# SCH_555-thing_2026-06-18.net
KiCad netlist of a schematic drawn in EasyEDA
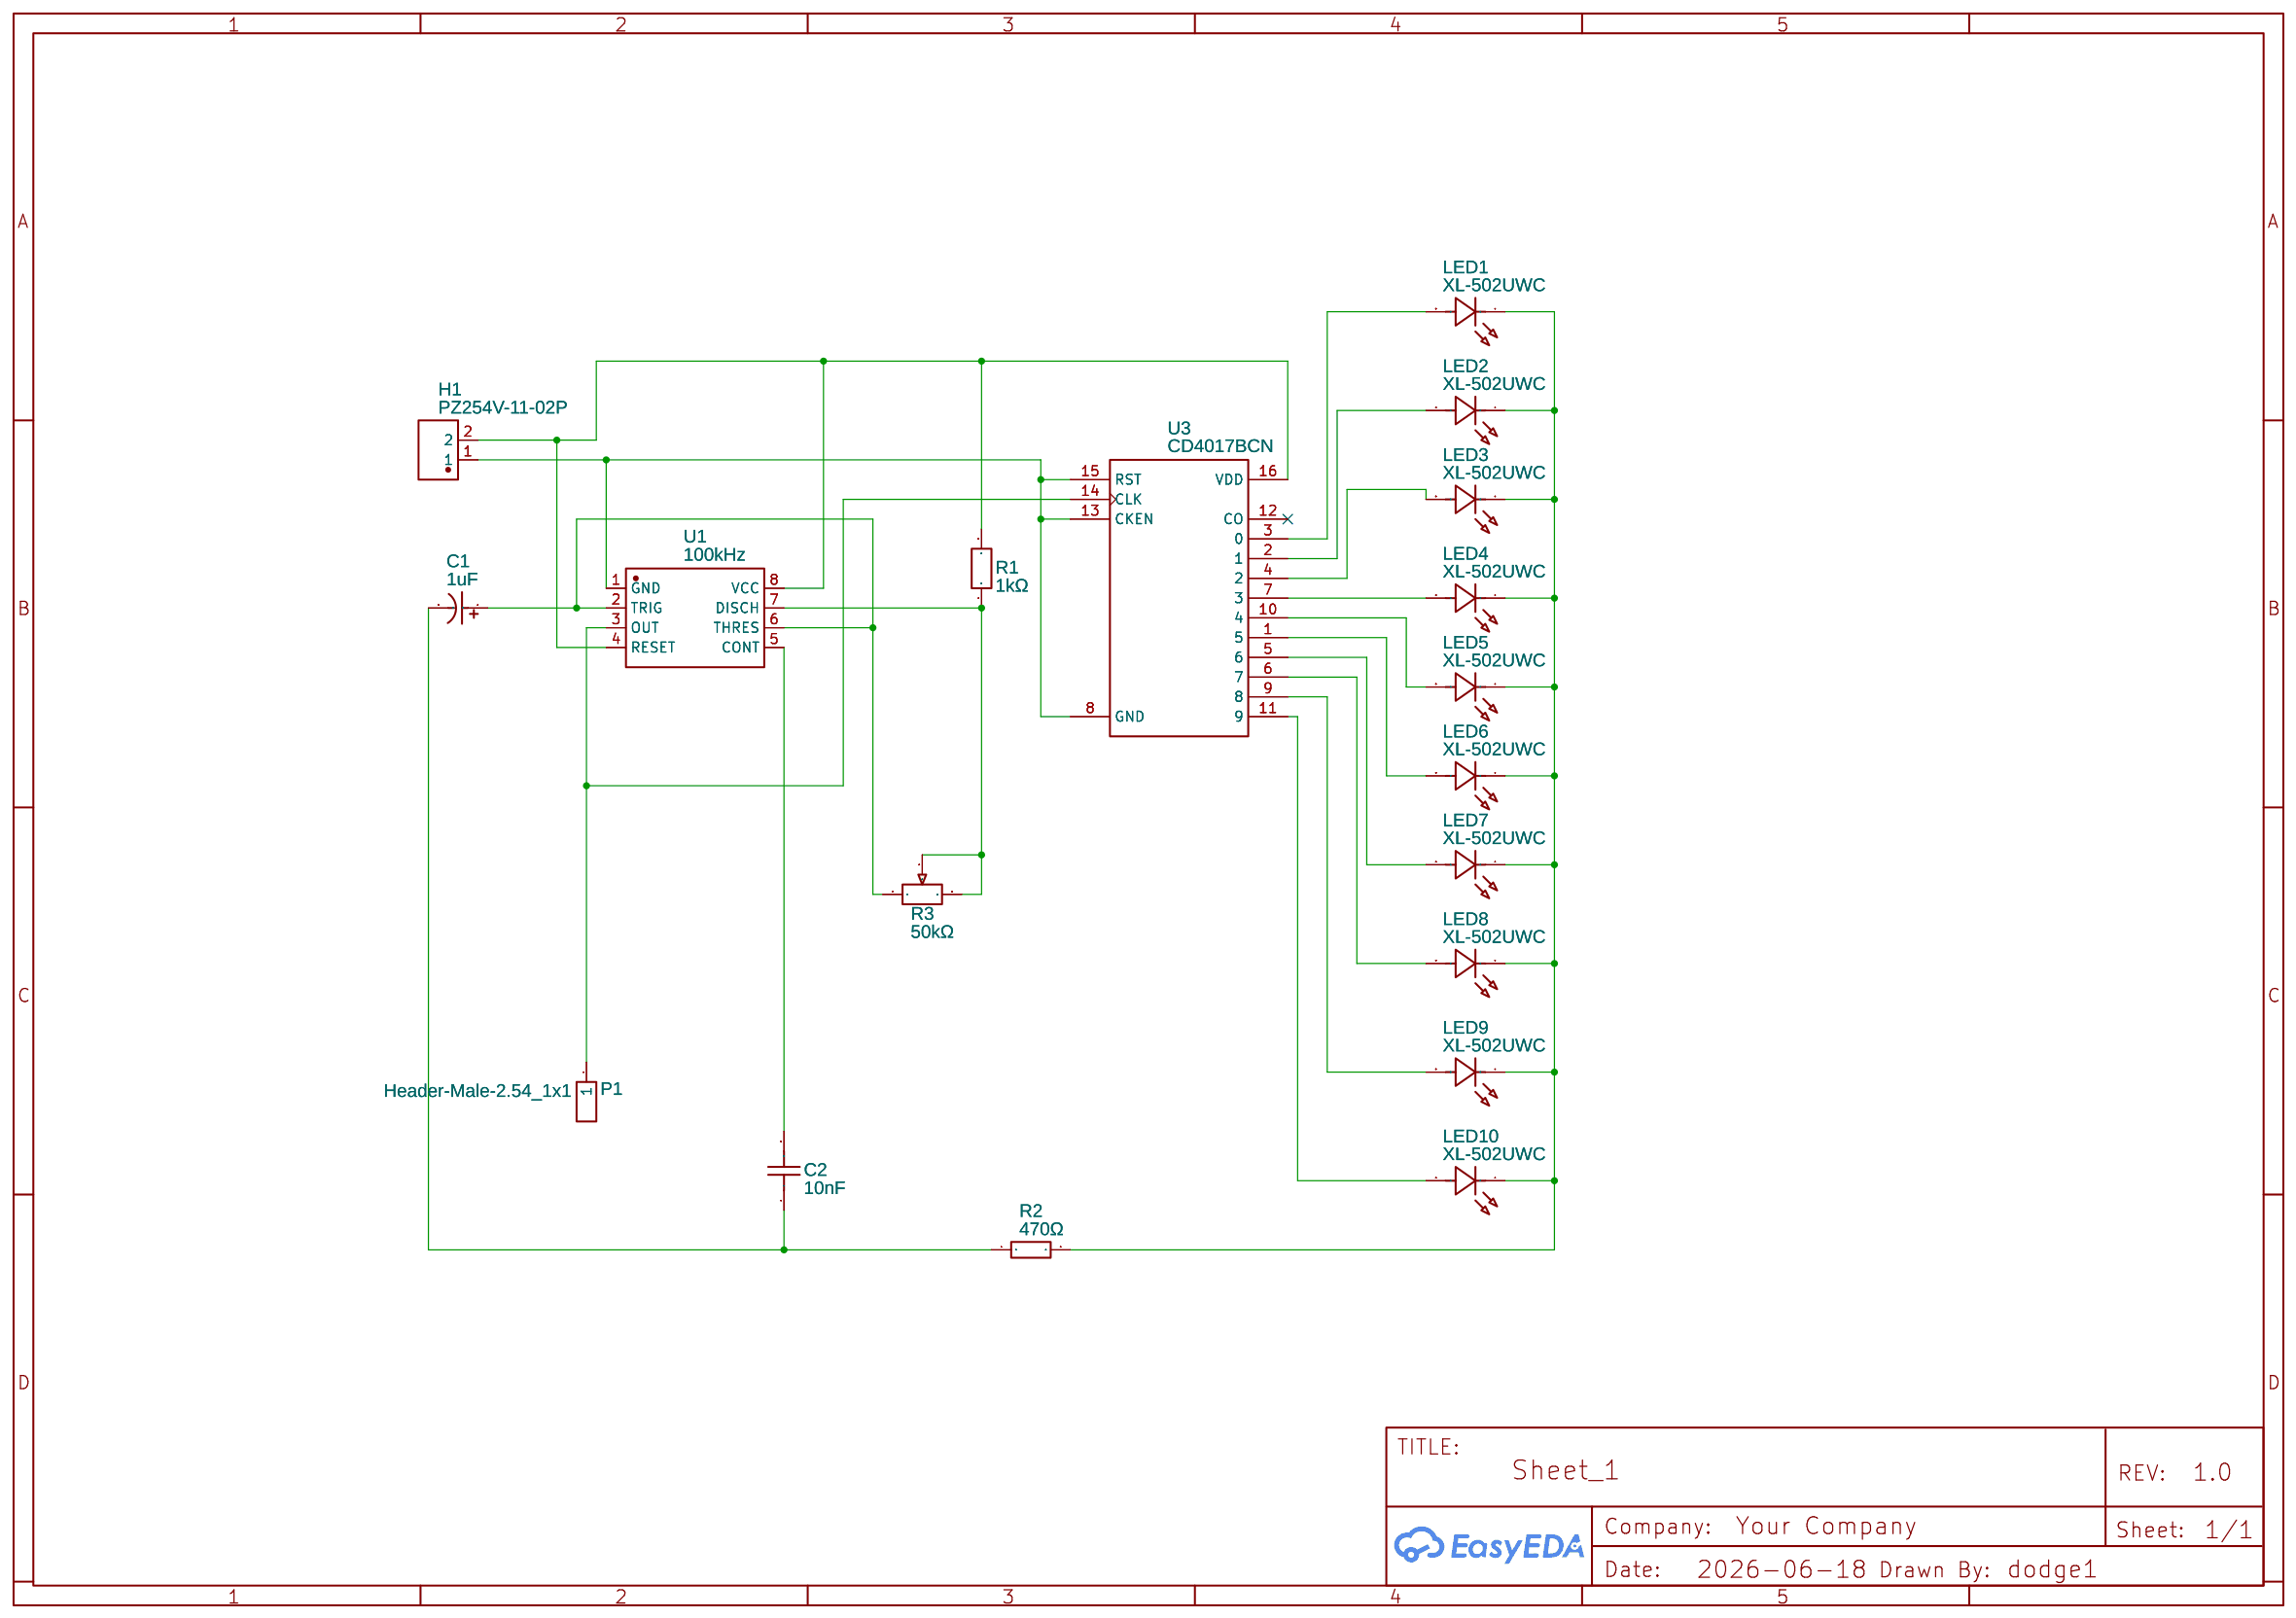
[diagram p0: schematic sheet]

(export (version "E")
  (design (tool "Eeschema 10.0.6"))
  (components
    (comp (ref "C1")
      (value "1uF")
      (fields (field (name "Manufacturer Part") "KF010M050C110A") (field (name "Manufacturer") "CapXon(丰宾)"))
      (libsource (lib "") (part "KF010M050C110A"))
    )
    (comp (ref "C2")
      (value "10nF")
      (fields (field (name "Manufacturer Part") "N09F1B103MN0B0S0N0") (field (name "Manufacturer") "STE(松田)"))
      (libsource (lib "") (part "N09F1B103MN0B0S0N0"))
    )
    (comp (ref "H1")
      (value "PZ254V-11-02P")
      (fields (field (name "Manufacturer") "XFCN(兴飞)"))
      (libsource (lib "") (part "PZ254V-11-02P"))
    )
    (comp (ref "LED1")
      (value "XL-502UWC")
      (fields (field (name "Manufacturer") "XINGLIGHT(成兴光)"))
      (libsource (lib "") (part "XL-502UWC"))
    )
    (comp (ref "LED2")
      (value "XL-502UWC")
      (fields (field (name "Manufacturer") "XINGLIGHT(成兴光)"))
      (libsource (lib "") (part "XL-502UWC"))
    )
    (comp (ref "LED3")
      (value "XL-502UWC")
      (fields (field (name "Manufacturer") "XINGLIGHT(成兴光)"))
      (libsource (lib "") (part "XL-502UWC"))
    )
    (comp (ref "LED4")
      (value "XL-502UWC")
      (fields (field (name "Manufacturer") "XINGLIGHT(成兴光)"))
      (libsource (lib "") (part "XL-502UWC"))
    )
    (comp (ref "LED5")
      (value "XL-502UWC")
      (fields (field (name "Manufacturer") "XINGLIGHT(成兴光)"))
      (libsource (lib "") (part "XL-502UWC"))
    )
    (comp (ref "LED6")
      (value "XL-502UWC")
      (fields (field (name "Manufacturer") "XINGLIGHT(成兴光)"))
      (libsource (lib "") (part "XL-502UWC"))
    )
    (comp (ref "LED7")
      (value "XL-502UWC")
      (fields (field (name "Manufacturer") "XINGLIGHT(成兴光)"))
      (libsource (lib "") (part "XL-502UWC"))
    )
    (comp (ref "LED8")
      (value "XL-502UWC")
      (fields (field (name "Manufacturer") "XINGLIGHT(成兴光)"))
      (libsource (lib "") (part "XL-502UWC"))
    )
    (comp (ref "LED9")
      (value "XL-502UWC")
      (fields (field (name "Manufacturer") "XINGLIGHT(成兴光)"))
      (libsource (lib "") (part "XL-502UWC"))
    )
    (comp (ref "LED10")
      (value "XL-502UWC")
      (fields (field (name "Manufacturer") "XINGLIGHT(成兴光)"))
      (libsource (lib "") (part "XL-502UWC"))
    )
    (comp (ref "P1")
      (value "Header-Male-2.54_1x1")
      (fields (field (name "Manufacturer Part") "2.54-1*1P针") (field (name "Manufacturer") "BOOMELE(博穆精密)"))
      (libsource (lib "") (part "Header-Male-2.54_1x1"))
    )
    (comp (ref "R1")
      (value "1kΩ")
      (fields (field (name "Manufacturer Part") "MF1/4W-1KΩ±1%T52") (field (name "Manufacturer") "华星机电"))
      (libsource (lib "") (part "MF1/4W-1KΩ±1%T52"))
    )
    (comp (ref "R2")
      (value "470Ω")
      (fields
        (field (name "Manufacturer Part") "MFR0W4F4700A50")
        (field (name "Manufacturer") "UNI-ROYAL(厚声)")
      )
      (libsource (lib "") (part "MFR0W4F4700A50"))
    )
    (comp (ref "R3")
      (value "50kΩ")
      (fields (field (name "Manufacturer Part") "3296X-1-503") (field (name "Manufacturer") "BOCHEN(博晨)"))
      (libsource (lib "") (part "3296X-1-503_C118912"))
    )
    (comp (ref "U1")
      (value "100kHz")
      (fields (field (name "Manufacturer Part") "NE555P") (field (name "Manufacturer") "TI(德州仪器)"))
      (libsource (lib "") (part "NE555P"))
    )
    (comp (ref "U3") (value "CD4017BCN") (libsource (lib "") (part "CD4017BCN")))
  )
  (nets
    (net (code "1") (name "Net-(C1-Pad2)") (class "Default")
      (node (ref "C1") (pin "2") (pinfunction "2_2") (pintype "input"))
      (node (ref "C2") (pin "1") (pinfunction "1_1") (pintype "unspecified"))
      (node (ref "R2") (pin "1") (pinfunction "1_1") (pintype "input"))
    )
    (net (code "2") (name "Net-(LED1-A)") (class "Default")
      (node (ref "LED1") (pin "2") (pinfunction "A_2") (pintype "unspecified"))
      (node (ref "U3") (pin "3") (pinfunction "0_3") (pintype "output"))
    )
    (net (code "3") (name "Net-(LED1-K)") (class "Default")
      (node (ref "LED1") (pin "1") (pinfunction "K_1") (pintype "unspecified"))
      (node (ref "LED10") (pin "1") (pinfunction "K_1") (pintype "unspecified"))
      (node (ref "LED2") (pin "1") (pinfunction "K_1") (pintype "unspecified"))
      (node (ref "LED3") (pin "1") (pinfunction "K_1") (pintype "unspecified"))
      (node (ref "LED4") (pin "1") (pinfunction "K_1") (pintype "unspecified"))
      (node (ref "LED5") (pin "1") (pinfunction "K_1") (pintype "unspecified"))
      (node (ref "LED6") (pin "1") (pinfunction "K_1") (pintype "unspecified"))
      (node (ref "LED7") (pin "1") (pinfunction "K_1") (pintype "unspecified"))
      (node (ref "LED8") (pin "1") (pinfunction "K_1") (pintype "unspecified"))
      (node (ref "LED9") (pin "1") (pinfunction "K_1") (pintype "unspecified"))
      (node (ref "R2") (pin "2") (pinfunction "2_2") (pintype "input"))
    )
    (net (code "4") (name "Net-(LED2-A)") (class "Default")
      (node (ref "LED2") (pin "2") (pinfunction "A_2") (pintype "unspecified"))
      (node (ref "U3") (pin "2") (pinfunction "1_2") (pintype "output"))
    )
    (net (code "5") (name "Net-(LED3-A)") (class "Default")
      (node (ref "LED3") (pin "2") (pinfunction "A_2") (pintype "unspecified"))
      (node (ref "U3") (pin "4") (pinfunction "2_4") (pintype "output"))
    )
    (net (code "6") (name "Net-(LED4-A)") (class "Default")
      (node (ref "LED4") (pin "2") (pinfunction "A_2") (pintype "unspecified"))
      (node (ref "U3") (pin "7") (pinfunction "3_7") (pintype "output"))
    )
    (net (code "7") (name "Net-(LED5-A)") (class "Default")
      (node (ref "LED5") (pin "2") (pinfunction "A_2") (pintype "unspecified"))
      (node (ref "U3") (pin "10") (pinfunction "4_10") (pintype "output"))
    )
    (net (code "8") (name "Net-(LED6-A)") (class "Default")
      (node (ref "LED6") (pin "2") (pinfunction "A_2") (pintype "unspecified"))
      (node (ref "U3") (pin "1") (pinfunction "5_1") (pintype "output"))
    )
    (net (code "9") (name "Net-(LED7-A)") (class "Default")
      (node (ref "LED7") (pin "2") (pinfunction "A_2") (pintype "unspecified"))
      (node (ref "U3") (pin "5") (pinfunction "6_5") (pintype "output"))
    )
    (net (code "10") (name "Net-(LED8-A)") (class "Default")
      (node (ref "LED8") (pin "2") (pinfunction "A_2") (pintype "unspecified"))
      (node (ref "U3") (pin "6") (pinfunction "7_6") (pintype "output"))
    )
    (net (code "11") (name "Net-(LED9-A)") (class "Default")
      (node (ref "LED9") (pin "2") (pinfunction "A_2") (pintype "unspecified"))
      (node (ref "U3") (pin "9") (pinfunction "8_9") (pintype "output"))
    )
    (net (code "12") (name "Net-(LED10-A)") (class "Default")
      (node (ref "LED10") (pin "2") (pinfunction "A_2") (pintype "unspecified"))
      (node (ref "U3") (pin "11") (pinfunction "9_11") (pintype "output"))
    )
    (net (code "13") (name "Net-(U1-CONT)") (class "Default")
      (node (ref "C2") (pin "2") (pinfunction "2_2") (pintype "unspecified"))
      (node (ref "U1") (pin "5") (pinfunction "CONT_5") (pintype "unspecified"))
    )
    (net (code "14") (name "Net-(U1-DISCH)") (class "Default")
      (node (ref "R1") (pin "1") (pinfunction "1_1") (pintype "unspecified"))
      (node (ref "R3") (pin "2") (pinfunction "2_2") (pintype "input"))
      (node (ref "R3") (pin "3") (pinfunction "3_3") (pintype "input"))
      (node (ref "U1") (pin "7") (pinfunction "DISCH_7") (pintype "unspecified"))
    )
    (net (code "15") (name "Net-(U1-GND)") (class "Default")
      (node (ref "H1") (pin "1") (pinfunction "1_1") (pintype "unspecified"))
      (node (ref "U1") (pin "1") (pinfunction "GND_1") (pintype "unspecified"))
      (node (ref "U3") (pin "13") (pinfunction "CKEN_13") (pintype "unspecified"))
      (node (ref "U3") (pin "15") (pinfunction "RST_15") (pintype "unspecified"))
      (node (ref "U3") (pin "8") (pinfunction "GND_8") (pintype "passive"))
    )
    (net (code "16") (name "Net-(U1-OUT)") (class "Default")
      (node (ref "P1") (pin "1") (pinfunction "1_1") (pintype "input"))
      (node (ref "U1") (pin "3") (pinfunction "OUT_3") (pintype "unspecified"))
      (node (ref "U3") (pin "14") (pinfunction "CLK_14") (pintype "unspecified"))
    )
    (net (code "17") (name "Net-(U1-RESET)") (class "Default")
      (node (ref "H1") (pin "2") (pinfunction "2_2") (pintype "unspecified"))
      (node (ref "R1") (pin "2") (pinfunction "2_2") (pintype "unspecified"))
      (node (ref "U1") (pin "4") (pinfunction "RESET_4") (pintype "unspecified"))
      (node (ref "U1") (pin "8") (pinfunction "VCC_8") (pintype "unspecified"))
      (node (ref "U3") (pin "16") (pinfunction "VDD_16") (pintype "passive"))
    )
    (net (code "18") (name "Net-(U1-THRES)") (class "Default")
      (node (ref "C1") (pin "1") (pinfunction "1_1") (pintype "input"))
      (node (ref "R3") (pin "1") (pinfunction "1_1") (pintype "input"))
      (node (ref "U1") (pin "2") (pinfunction "TRIG_2") (pintype "unspecified"))
      (node (ref "U1") (pin "6") (pinfunction "THRES_6") (pintype "unspecified"))
    )
    (net (code "19") (name "unconnected-(U3-CO-Pad12)") (class "Default")
      (node (ref "U3") (pin "12") (pinfunction "CO_12") (pintype "output+no_connect"))
    )
  )
)
